# RF2.net
KiCad netlist of a schematic drawn in Altium Designer
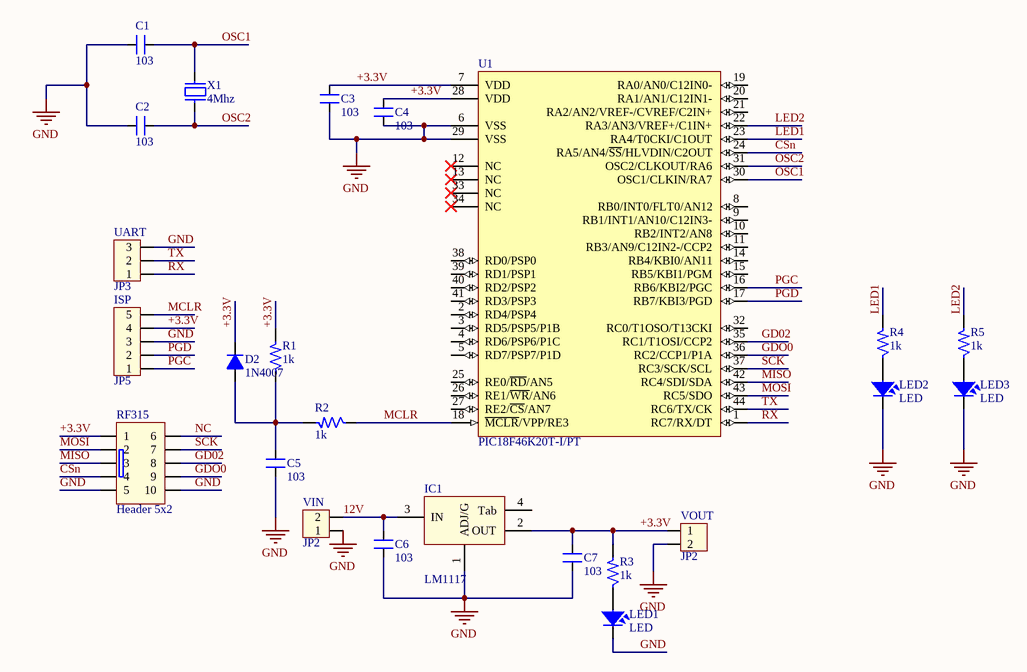
[diagram p0: RF2.SchDoc]

(export (version "E")
  (design (tool "Eeschema 10.0.6"))
  (components
    (comp (ref "C1")
      (value "103")
      (footprint "SM-0805")
      (description "Cap SMD")
      (libsource (lib "syhaunguyen") (part "CM"))
    )
    (comp (ref "C2")
      (value "103")
      (footprint "SM-0805")
      (description "Cap SMD")
      (libsource (lib "syhaunguyen") (part "CM"))
    )
    (comp (ref "C3")
      (value "103")
      (footprint "SM-0805")
      (description "Cap SMD")
      (libsource (lib "syhaunguyen") (part "CM"))
    )
    (comp (ref "C4")
      (value "103")
      (footprint "SM-0805")
      (description "Cap SMD")
      (libsource (lib "syhaunguyen") (part "CM"))
    )
    (comp (ref "C5")
      (value "103")
      (footprint "SM-0805")
      (description "Cap SMD")
      (libsource (lib "syhaunguyen") (part "CM"))
    )
    (comp (ref "C6")
      (value "103")
      (footprint "SM-0805")
      (description "Cap SMD")
      (libsource (lib "syhaunguyen") (part "CM"))
    )
    (comp (ref "C7")
      (value "103")
      (footprint "SM-0805")
      (description "Cap SMD")
      (libsource (lib "syhaunguyen") (part "CM"))
    )
    (comp (ref "D2")
      (value "1N4007")
      (footprint "SM-DIODE")
      (description "Diode 1A")
      (libsource (lib "syhaunguyen") (part "D1A"))
    )
    (comp (ref "IC1")
      (value "LM1117")
      (footprint "SOT223-4N")
      (description "3v3")
      (libsource (lib "syhaunguyen") (part "LM1117"))
    )
    (comp (ref "ISP")
      (value "JP5")
      (footprint "CON5")
      (description "Connector 5")
      (libsource (lib "syhaunguyen") (part "Con5"))
    )
    (comp (ref "LED1")
      (value "LED")
      (footprint "LED-3")
      (description "LED Single colour Green and Red")
      (libsource (lib "syhaunguyen") (part "LED"))
    )
    (comp (ref "LED2")
      (value "LED")
      (footprint "LED-3")
      (description "LED Single colour Green and Red")
      (libsource (lib "syhaunguyen") (part "LED"))
    )
    (comp (ref "LED3")
      (value "LED")
      (footprint "LED-3")
      (description "LED Single colour Green and Red")
      (libsource (lib "syhaunguyen") (part "LED"))
    )
    (comp (ref "R1")
      (value "1k")
      (footprint "SM-0805")
      (description "Resistor 1/4W")
      (libsource (lib "syhaunguyen") (part "R"))
    )
    (comp (ref "R2")
      (value "1k")
      (footprint "SM-0805")
      (description "Resistor 1/4W")
      (libsource (lib "syhaunguyen") (part "R"))
    )
    (comp (ref "R3")
      (value "1k")
      (footprint "SM-0805")
      (description "Resistor 1/4W")
      (libsource (lib "syhaunguyen") (part "R"))
    )
    (comp (ref "R4")
      (value "1k")
      (footprint "SM-0805")
      (description "Resistor 1/4W")
      (libsource (lib "syhaunguyen") (part "R"))
    )
    (comp (ref "R5")
      (value "1k")
      (footprint "SM-0805")
      (description "Resistor 1/4W")
      (libsource (lib "syhaunguyen") (part "R"))
    )
    (comp (ref "RF315")
      (value "Header 5x2")
      (footprint "HED2X5_cen")
      (libsource (lib "syhaunguyen") (part "HED5x2"))
    )
    (comp (ref "U1")
      (value "PIC18F46K20T-I/PT")
      (footprint "TQFP-PT44_N")
      (fields (field (name "PUBLISHER") "Altium Limited"))
      (libsource (lib "ChuTrongKhanh") (part "PIC18F46K20T-I/PT"))
    )
    (comp (ref "UART")
      (value "JP3")
      (footprint "CON3")
      (description "Connector 3")
      (libsource (lib "syhaunguyen") (part "Con3"))
    )
    (comp (ref "VIN")
      (value "JP2")
      (footprint "CON2")
      (description "Connector 2")
      (libsource (lib "") (part "Con2_1"))
    )
    (comp (ref "VOUT")
      (value "JP2")
      (footprint "CON2")
      (description "Connector 2")
      (libsource (lib "syhaunguyen") (part "Con2"))
    )
    (comp (ref "X1")
      (value "4Mhz")
      (footprint "XT2")
      (description "Crystal For all Crystal 2pin.")
      (libsource (lib "syhaunguyen") (part "XT2"))
    )
  )
  (nets
    (net (code "1") (name "/+3.3V") (class "Default")
      (node (ref "C3") (pin "2") (pinfunction "2_2") (pintype "passive"))
      (node (ref "C4") (pin "2") (pinfunction "2_2") (pintype "passive"))
      (node (ref "C7") (pin "2") (pinfunction "2_2") (pintype "passive"))
      (node (ref "D2") (pin "2") (pinfunction "K_2") (pintype "passive"))
      (node (ref "IC1") (pin "2") (pinfunction "OUT_2") (pintype "passive"))
      (node (ref "ISP") (pin "4") (pinfunction "4_4") (pintype "passive"))
      (node (ref "R1") (pin "2") (pinfunction "2_2") (pintype "passive"))
      (node (ref "R3") (pin "2") (pinfunction "2_2") (pintype "passive"))
      (node (ref "RF315") (pin "1") (pinfunction "1_1") (pintype "passive"))
      (node (ref "U1") (pin "28") (pinfunction "VDD_28") (pintype "power_in"))
      (node (ref "U1") (pin "7") (pinfunction "VDD_7") (pintype "power_in"))
      (node (ref "VOUT") (pin "1") (pinfunction "1_1") (pintype "passive"))
    )
    (net (code "2") (name "/12V") (class "Default")
      (node (ref "C6") (pin "2") (pinfunction "2_2") (pintype "passive"))
      (node (ref "IC1") (pin "3") (pinfunction "IN_3") (pintype "passive"))
      (node (ref "VIN") (pin "2") (pinfunction "2_2") (pintype "passive"))
    )
    (net (code "3") (name "/CSn") (class "Default")
      (node (ref "RF315") (pin "4") (pinfunction "4_4") (pintype "passive"))
      (node (ref "U1") (pin "24") (pinfunction "RA5/AN4/~{SS}/HLVDIN/C2OUT_24") (pintype "bidirectional"))
    )
    (net (code "4") (name "/GD02") (class "Default")
      (node (ref "RF315") (pin "8") (pinfunction "8_8") (pintype "passive"))
      (node (ref "U1") (pin "35") (pinfunction "RC1/T1OSI/CCP2_35") (pintype "bidirectional"))
    )
    (net (code "5") (name "/GDO0") (class "Default")
      (node (ref "RF315") (pin "9") (pinfunction "9_9") (pintype "passive"))
      (node (ref "U1") (pin "36") (pinfunction "RC2/CCP1/P1A_36") (pintype "bidirectional"))
    )
    (net (code "6") (name "/LED1") (class "Default")
      (node (ref "R4") (pin "2") (pinfunction "2_2") (pintype "passive"))
      (node (ref "U1") (pin "23") (pinfunction "RA4/T0CKI/C1OUT_23") (pintype "bidirectional"))
    )
    (net (code "7") (name "/LED2") (class "Default")
      (node (ref "R5") (pin "2") (pinfunction "2_2") (pintype "passive"))
      (node (ref "U1") (pin "22") (pinfunction "RA3/AN3/VREF+/C1IN+_22") (pintype "bidirectional"))
    )
    (net (code "8") (name "/MCLR") (class "Default")
      (node (ref "ISP") (pin "5") (pinfunction "5_5") (pintype "passive"))
      (node (ref "R2") (pin "1") (pinfunction "1_1") (pintype "passive"))
      (node (ref "U1") (pin "18") (pinfunction "~{MCLR}/VPP/RE3_18") (pintype "input"))
    )
    (net (code "9") (name "/MISO") (class "Default")
      (node (ref "RF315") (pin "3") (pinfunction "3_3") (pintype "passive"))
      (node (ref "U1") (pin "42") (pinfunction "RC4/SDI/SDA_42") (pintype "bidirectional"))
    )
    (net (code "10") (name "/MOSI") (class "Default")
      (node (ref "RF315") (pin "2") (pinfunction "2_2") (pintype "passive"))
      (node (ref "U1") (pin "43") (pinfunction "RC5/SDO_43") (pintype "bidirectional"))
    )
    (net (code "11") (name "/NC") (class "Default")
      (node (ref "RF315") (pin "6") (pinfunction "6_6") (pintype "passive"))
    )
    (net (code "12") (name "/OSC1") (class "Default")
      (node (ref "C1") (pin "2") (pinfunction "2_2") (pintype "passive"))
      (node (ref "U1") (pin "30") (pinfunction "OSC1/CLKIN/RA7_30") (pintype "bidirectional"))
      (node (ref "X1") (pin "2") (pinfunction "2_2") (pintype "passive"))
    )
    (net (code "13") (name "/OSC2") (class "Default")
      (node (ref "C2") (pin "2") (pinfunction "2_2") (pintype "passive"))
      (node (ref "U1") (pin "31") (pinfunction "OSC2/CLKOUT/RA6_31") (pintype "bidirectional"))
      (node (ref "X1") (pin "1") (pinfunction "1_1") (pintype "passive"))
    )
    (net (code "14") (name "/PGC") (class "Default")
      (node (ref "ISP") (pin "1") (pinfunction "1_1") (pintype "passive"))
      (node (ref "U1") (pin "16") (pinfunction "RB6/KBI2/PGC_16") (pintype "bidirectional"))
    )
    (net (code "15") (name "/PGD") (class "Default")
      (node (ref "ISP") (pin "2") (pinfunction "2_2") (pintype "passive"))
      (node (ref "U1") (pin "17") (pinfunction "RB7/KBI3/PGD_17") (pintype "bidirectional"))
    )
    (net (code "16") (name "/RX") (class "Default")
      (node (ref "U1") (pin "1") (pinfunction "RC7/RX/DT_1") (pintype "bidirectional"))
      (node (ref "UART") (pin "1") (pinfunction "1_1") (pintype "passive"))
    )
    (net (code "17") (name "/SCK") (class "Default")
      (node (ref "RF315") (pin "7") (pinfunction "7_7") (pintype "passive"))
      (node (ref "U1") (pin "37") (pinfunction "RC3/SCK/SCL_37") (pintype "bidirectional"))
    )
    (net (code "18") (name "/TX") (class "Default")
      (node (ref "U1") (pin "44") (pinfunction "RC6/TX/CK_44") (pintype "bidirectional"))
      (node (ref "UART") (pin "2") (pinfunction "2_2") (pintype "passive"))
    )
    (net (code "19") (name "GND") (class "Default")
      (node (ref "C1") (pin "1") (pinfunction "1_1") (pintype "passive"))
      (node (ref "C2") (pin "1") (pinfunction "1_1") (pintype "passive"))
      (node (ref "C3") (pin "1") (pinfunction "1_1") (pintype "passive"))
      (node (ref "C4") (pin "1") (pinfunction "1_1") (pintype "passive"))
      (node (ref "C5") (pin "1") (pinfunction "1_1") (pintype "passive"))
      (node (ref "C6") (pin "1") (pinfunction "1_1") (pintype "passive"))
      (node (ref "C7") (pin "1") (pinfunction "1_1") (pintype "passive"))
      (node (ref "IC1") (pin "1") (pinfunction "ADJ/G_1") (pintype "passive"))
      (node (ref "ISP") (pin "3") (pinfunction "3_3") (pintype "passive"))
      (node (ref "LED1") (pin "2") (pinfunction "2_2") (pintype "passive"))
      (node (ref "LED2") (pin "2") (pinfunction "2_2") (pintype "passive"))
      (node (ref "LED3") (pin "2") (pinfunction "2_2") (pintype "passive"))
      (node (ref "RF315") (pin "10") (pinfunction "10_10") (pintype "passive"))
      (node (ref "RF315") (pin "5") (pinfunction "5_5") (pintype "passive"))
      (node (ref "U1") (pin "29") (pinfunction "VSS_29") (pintype "power_in"))
      (node (ref "U1") (pin "6") (pinfunction "VSS_6") (pintype "power_in"))
      (node (ref "UART") (pin "3") (pinfunction "3_3") (pintype "passive"))
      (node (ref "VIN") (pin "1") (pinfunction "1_1") (pintype "passive"))
      (node (ref "VOUT") (pin "2") (pinfunction "2_2") (pintype "passive"))
    )
    (net (code "20") (name "Net-(D2-A)") (class "Default")
      (node (ref "C5") (pin "2") (pinfunction "2_2") (pintype "passive"))
      (node (ref "D2") (pin "1") (pinfunction "A_1") (pintype "passive"))
      (node (ref "R1") (pin "1") (pinfunction "1_1") (pintype "passive"))
      (node (ref "R2") (pin "2") (pinfunction "2_2") (pintype "passive"))
    )
    (net (code "21") (name "Net-(LED1-Pad1)") (class "Default")
      (node (ref "LED1") (pin "1") (pinfunction "1_1") (pintype "passive"))
      (node (ref "R3") (pin "1") (pinfunction "1_1") (pintype "passive"))
    )
    (net (code "22") (name "Net-(LED2-Pad1)") (class "Default")
      (node (ref "LED2") (pin "1") (pinfunction "1_1") (pintype "passive"))
      (node (ref "R4") (pin "1") (pinfunction "1_1") (pintype "passive"))
    )
    (net (code "23") (name "Net-(LED3-Pad1)") (class "Default")
      (node (ref "LED3") (pin "1") (pinfunction "1_1") (pintype "passive"))
      (node (ref "R5") (pin "1") (pinfunction "1_1") (pintype "passive"))
    )
    (net (code "24") (name "unconnected-(IC1-Tab-Pad4)") (class "Default")
      (node (ref "IC1") (pin "4") (pinfunction "Tab_4") (pintype "passive"))
    )
    (net (code "25") (name "unconnected-(U1-NC-Pad12)") (class "Default")
      (node (ref "U1") (pin "12") (pinfunction "NC_12") (pintype "passive+no_connect"))
    )
    (net (code "26") (name "unconnected-(U1-NC-Pad13)") (class "Default")
      (node (ref "U1") (pin "13") (pinfunction "NC_13") (pintype "passive+no_connect"))
    )
    (net (code "27") (name "unconnected-(U1-NC-Pad33)") (class "Default")
      (node (ref "U1") (pin "33") (pinfunction "NC_33") (pintype "passive+no_connect"))
    )
    (net (code "28") (name "unconnected-(U1-NC-Pad34)") (class "Default")
      (node (ref "U1") (pin "34") (pinfunction "NC_34") (pintype "passive+no_connect"))
    )
    (net (code "29") (name "unconnected-(U1-RA0{slash}AN0{slash}C12IN0--Pad19)") (class "Default")
      (node (ref "U1") (pin "19") (pinfunction "RA0/AN0/C12IN0-_19") (pintype "bidirectional"))
    )
    (net (code "30") (name "unconnected-(U1-RA1{slash}AN1{slash}C12IN1--Pad20)") (class "Default")
      (node (ref "U1") (pin "20") (pinfunction "RA1/AN1/C12IN1-_20") (pintype "bidirectional"))
    )
    (net (code "31") (name "unconnected-(U1-RA2{slash}AN2{slash}VREF-{slash}CVREF{slash}C2IN+-Pad21)") (class "Default")
      (node (ref "U1") (pin "21") (pinfunction "RA2/AN2/VREF-/CVREF/C2IN+_21") (pintype "bidirectional"))
    )
    (net (code "32") (name "unconnected-(U1-RB0{slash}INT0{slash}FLT0{slash}AN12-Pad8)") (class "Default")
      (node (ref "U1") (pin "8") (pinfunction "RB0/INT0/FLT0/AN12_8") (pintype "bidirectional"))
    )
    (net (code "33") (name "unconnected-(U1-RB1{slash}INT1{slash}AN10{slash}C12IN3--Pad9)") (class "Default")
      (node (ref "U1") (pin "9") (pinfunction "RB1/INT1/AN10/C12IN3-_9") (pintype "bidirectional"))
    )
    (net (code "34") (name "unconnected-(U1-RB2{slash}INT2{slash}AN8-Pad10)") (class "Default")
      (node (ref "U1") (pin "10") (pinfunction "RB2/INT2/AN8_10") (pintype "bidirectional"))
    )
    (net (code "35") (name "unconnected-(U1-RB3{slash}AN9{slash}C12IN2-{slash}CCP2-Pad11)") (class "Default")
      (node (ref "U1") (pin "11") (pinfunction "RB3/AN9/C12IN2-/CCP2_11") (pintype "bidirectional"))
    )
    (net (code "36") (name "unconnected-(U1-RB4{slash}KBI0{slash}AN11-Pad14)") (class "Default")
      (node (ref "U1") (pin "14") (pinfunction "RB4/KBI0/AN11_14") (pintype "bidirectional"))
    )
    (net (code "37") (name "unconnected-(U1-RB5{slash}KBI1{slash}PGM-Pad15)") (class "Default")
      (node (ref "U1") (pin "15") (pinfunction "RB5/KBI1/PGM_15") (pintype "bidirectional"))
    )
    (net (code "38") (name "unconnected-(U1-RC0{slash}T1OSO{slash}T13CKI-Pad32)") (class "Default")
      (node (ref "U1") (pin "32") (pinfunction "RC0/T1OSO/T13CKI_32") (pintype "bidirectional"))
    )
    (net (code "39") (name "unconnected-(U1-RD0{slash}PSP0-Pad38)") (class "Default")
      (node (ref "U1") (pin "38") (pinfunction "RD0/PSP0_38") (pintype "bidirectional"))
    )
    (net (code "40") (name "unconnected-(U1-RD1{slash}PSP1-Pad39)") (class "Default")
      (node (ref "U1") (pin "39") (pinfunction "RD1/PSP1_39") (pintype "bidirectional"))
    )
    (net (code "41") (name "unconnected-(U1-RD2{slash}PSP2-Pad40)") (class "Default")
      (node (ref "U1") (pin "40") (pinfunction "RD2/PSP2_40") (pintype "bidirectional"))
    )
    (net (code "42") (name "unconnected-(U1-RD3{slash}PSP3-Pad41)") (class "Default")
      (node (ref "U1") (pin "41") (pinfunction "RD3/PSP3_41") (pintype "bidirectional"))
    )
    (net (code "43") (name "unconnected-(U1-RD4{slash}PSP4-Pad2)") (class "Default")
      (node (ref "U1") (pin "2") (pinfunction "RD4/PSP4_2") (pintype "bidirectional"))
    )
    (net (code "44") (name "unconnected-(U1-RD5{slash}PSP5{slash}P1B-Pad3)") (class "Default")
      (node (ref "U1") (pin "3") (pinfunction "RD5/PSP5/P1B_3") (pintype "bidirectional"))
    )
    (net (code "45") (name "unconnected-(U1-RD6{slash}PSP6{slash}P1C-Pad4)") (class "Default")
      (node (ref "U1") (pin "4") (pinfunction "RD6/PSP6/P1C_4") (pintype "bidirectional"))
    )
    (net (code "46") (name "unconnected-(U1-RD7{slash}PSP7{slash}P1D-Pad5)") (class "Default")
      (node (ref "U1") (pin "5") (pinfunction "RD7/PSP7/P1D_5") (pintype "bidirectional"))
    )
    (net (code "47") (name "unconnected-(U1-RE0{slash}~{RD}{slash}AN5-Pad25)") (class "Default")
      (node (ref "U1") (pin "25") (pinfunction "RE0/~{RD}/AN5_25") (pintype "bidirectional"))
    )
    (net (code "48") (name "unconnected-(U1-RE1{slash}~{WR}{slash}AN6-Pad26)") (class "Default")
      (node (ref "U1") (pin "26") (pinfunction "RE1/~{WR}/AN6_26") (pintype "bidirectional"))
    )
    (net (code "49") (name "unconnected-(U1-RE2{slash}~{CS}{slash}AN7-Pad27)") (class "Default")
      (node (ref "U1") (pin "27") (pinfunction "RE2/~{CS}/AN7_27") (pintype "bidirectional"))
    )
  )
)
